# pir-piezo.net
KiCad netlist of a schematic drawn in Altium Designer
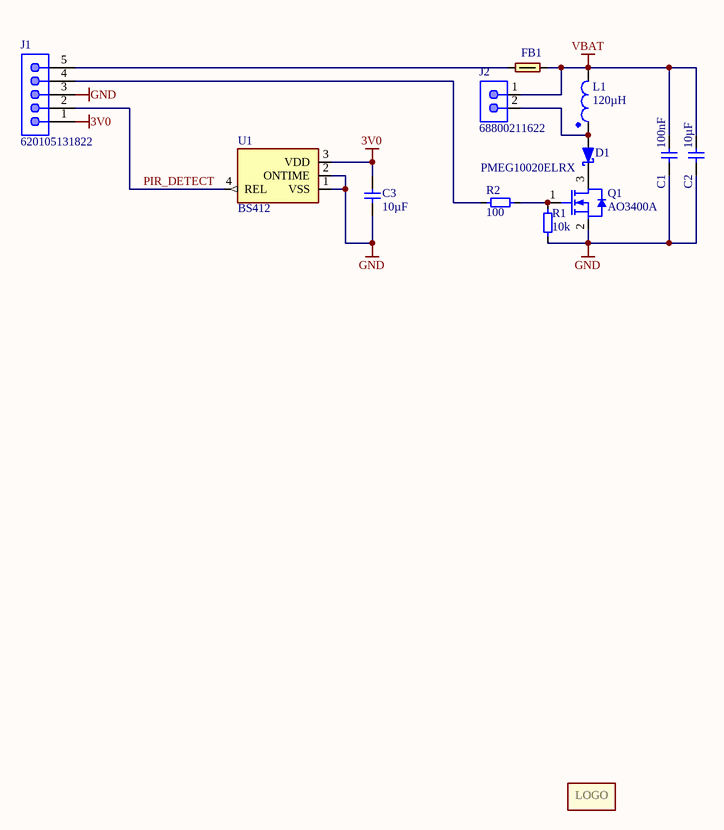
[diagram p0: pir-piezo.SchDoc]

(export (version "E")
  (design (tool "Eeschema 10.0.6"))
  (components
    (comp (ref "C1")
      (value "100nF")
      (footprint "0603-C-N")
      (description "WCAP-CSGP Multilayer Ceramic Chip Capacitor, General Purpose, size 0603, X7R, 100nF, 25VDC")
      (fields (field (name "FLIR PART #") "YCAM100N-5") (field (name "JLCPCB PART #") "C14663"))
      (libsource (lib "7c7 Engineering") (part "CAP-NP-2"))
    )
    (comp (ref "C2")
      (value "10µF")
      (footprint "1206-C-N")
      (description "WCAP-CSGP Multilayer Ceramic Chip Capacitor, General Purpose, size 1206, X7R, 10µF, 10VDC")
      (fields (field (name "JLCPCB PART #") "C70462") (field (name "TOLERANCE") "10%"))
      (libsource (lib "7c7 Engineering") (part "CAP-NP-2"))
    )
    (comp (ref "C3")
      (value "10µF")
      (footprint "1206-C-N")
      (description "WCAP-CSGP Multilayer Ceramic Chip Capacitor, General Purpose, size 1206, X7R, 10µF, 10VDC")
      (fields (field (name "JLCPCB PART #") "C70462") (field (name "TOLERANCE") "10%"))
      (libsource (lib "7c7 Engineering") (part "CAP-NP-2"))
    )
    (comp (ref "D1")
      (value "PMEG10020ELRX")
      (footprint "FP-SOD123W-MFG")
      (description "Diode Schottky 100V 2A 2-Pin SOD-123F T/R")
      (fields (field (name "JLCPCB PART #") "C456130"))
      (libsource (lib "7c7 Engineering") (part "DIODE-SKY-2"))
    )
    (comp (ref "FB1")
      (value "742792625")
      (footprint "0603-L-N")
      (description "WE-CBF SMT EMI Suppression Ferrite Bead, size 0603, 120O, 2A")
      (fields (field (name "MANUFACTURER") "Wurth Elektronik") (field (name "JLCPCB PART #") "C114770"))
      (libsource (lib "7c7 Engineering") (part "IND_BEAD"))
    )
    (comp (ref "J1")
      (value "620105131822")
      (footprint "620105131822")
      (description "WR-WTB SMT Male Horizontal Shrouded Header, pitch 2mm, 5p")
      (fields (field (name "JLCPCB PART #") "C265104") (field (name "PUBLISHER") "Wurth Elektronik"))
      (libsource (lib "7c7 Engineering") (part "HDR_5P"))
    )
    (comp (ref "J2")
      (value "68800211622")
      (footprint "68800211622")
      (description "WR-WTB “J” Type THT Vertical Male Shrouded Header, pitch 2.5mm, 2p")
      (fields (field (name "JLCPCB PART #") "C160262") (field (name "PUBLISHER") "Wurth Elektronik"))
      (libsource (lib "7c7 Engineering") (part "Symbol"))
    )
    (comp (ref "L1")
      (value "74404064121")
      (footprint "CL_STD6060")
      (description "WE-LQS SMT Power Inductor, size 6045, 120µH, 0.85A, 0.52O")
      (fields (field (name "MANUFACTURER") "Wurth Elektronik") (field (name "INDUCTANCE") "120µH"))
      (libsource (lib "7c7 Engineering") (part "IND_POLAR-2"))
    )
    (comp (ref "M1")
      (value "Logo")
      (footprint "LOGO_9x6mm")
      (libsource (lib "Integrated_Library_LieBtrau") (part "Logo"))
    )
    (comp (ref "Q1")
      (value "AO3400A")
      (footprint "SOT-23-3-N")
      (description "Trans MOSFET N-CH 30V 5.7A 3-Pin SOT-23")
      (fields (field (name "JLCPCB PART #") "C20917"))
      (libsource (lib "7c7 Engineering") (part "NMOS_NO_PROTECTION"))
    )
    (comp (ref "R1")
      (value "10k")
      (footprint "0603-R-N")
      (description "Chip Resistor, Thick Film, General Purpose, 0603, 100mW, 50V, 10 kOhm, +/-1%")
      (fields (field (name "TOLERANCE") "1%") (field (name "JLCPCB PART #") "C25804"))
      (libsource (lib "7c7 Engineering") (part "RES"))
    )
    (comp (ref "R2")
      (value "100")
      (footprint "0603-R-N")
      (description "Chip Resistor, Thick Film, General Purpose, 0603, 63mW, 50V, 100 Ohm, +/-1%")
      (fields (field (name "TOLERANCE") "1%") (field (name "JLCPCB PART #") "C22775"))
      (libsource (lib "") (part "RES_1"))
    )
    (comp (ref "U1")
      (value "BS412")
      (footprint "BS412-Footprint-1")
      (description "Mini Basic PIR Sensor - BS412")
      (fields (field (name "JLCPCB PART #") "C410378"))
      (libsource (lib "7c7 Engineering") (part "BS412-Symbol-1"))
    )
  )
  (nets
    (net (code "1") (name "/PIR_DETECT") (class "Default")
      (node (ref "J1") (pin "2") (pinfunction "2_2") (pintype "passive"))
      (node (ref "U1") (pin "4") (pinfunction "REL_4") (pintype "output"))
    )
    (net (code "2") (name "3V0") (class "Default")
      (node (ref "C3") (pin "1") (pinfunction "1_1") (pintype "passive"))
      (node (ref "J1") (pin "1") (pinfunction "1_1") (pintype "passive"))
      (node (ref "U1") (pin "3") (pinfunction "VDD_3") (pintype "power_in"))
    )
    (net (code "3") (name "GND") (class "Default")
      (node (ref "C1") (pin "2") (pinfunction "2_2") (pintype "passive"))
      (node (ref "C2") (pin "1") (pinfunction "1_1") (pintype "passive"))
      (node (ref "C3") (pin "2") (pinfunction "2_2") (pintype "passive"))
      (node (ref "J1") (pin "3") (pinfunction "3_3") (pintype "passive"))
      (node (ref "Q1") (pin "2") (pinfunction "S_2") (pintype "passive"))
      (node (ref "R1") (pin "2") (pinfunction "2_2") (pintype "passive"))
      (node (ref "U1") (pin "1") (pinfunction "VSS_1") (pintype "power_in"))
      (node (ref "U1") (pin "2") (pinfunction "ONTIME_2") (pintype "passive"))
    )
    (net (code "4") (name "Net-(D1-A)") (class "Default")
      (node (ref "D1") (pin "2") (pinfunction "A_2") (pintype "passive"))
      (node (ref "J2") (pin "2") (pinfunction "2_2") (pintype "passive"))
      (node (ref "L1") (pin "1") (pinfunction "1_1") (pintype "passive"))
    )
    (net (code "5") (name "Net-(D1-K)") (class "Default")
      (node (ref "D1") (pin "1") (pinfunction "K_1") (pintype "passive"))
      (node (ref "Q1") (pin "3") (pinfunction "D_3") (pintype "passive"))
    )
    (net (code "6") (name "Net-(FB1-Pad1)") (class "Default")
      (node (ref "FB1") (pin "1") (pinfunction "1_1") (pintype "passive"))
      (node (ref "J1") (pin "5") (pinfunction "5_5") (pintype "passive"))
    )
    (net (code "7") (name "Net-(J1-Pad4)") (class "Default")
      (node (ref "J1") (pin "4") (pinfunction "4_4") (pintype "passive"))
      (node (ref "R2") (pin "1") (pinfunction "1_1") (pintype "passive"))
    )
    (net (code "8") (name "Net-(Q1-G)") (class "Default")
      (node (ref "Q1") (pin "1") (pinfunction "G_1") (pintype "passive"))
      (node (ref "R1") (pin "1") (pinfunction "1_1") (pintype "passive"))
      (node (ref "R2") (pin "2") (pinfunction "2_2") (pintype "passive"))
    )
    (net (code "9") (name "VBAT") (class "Default")
      (node (ref "C1") (pin "1") (pinfunction "1_1") (pintype "passive"))
      (node (ref "C2") (pin "2") (pinfunction "2_2") (pintype "passive"))
      (node (ref "FB1") (pin "2") (pinfunction "2_2") (pintype "passive"))
      (node (ref "J2") (pin "1") (pinfunction "1_1") (pintype "passive"))
      (node (ref "L1") (pin "2") (pinfunction "2_2") (pintype "passive"))
    )
  )
)
